# EXT_SEC.net
KiCad netlist of a schematic drawn in Altium Designer
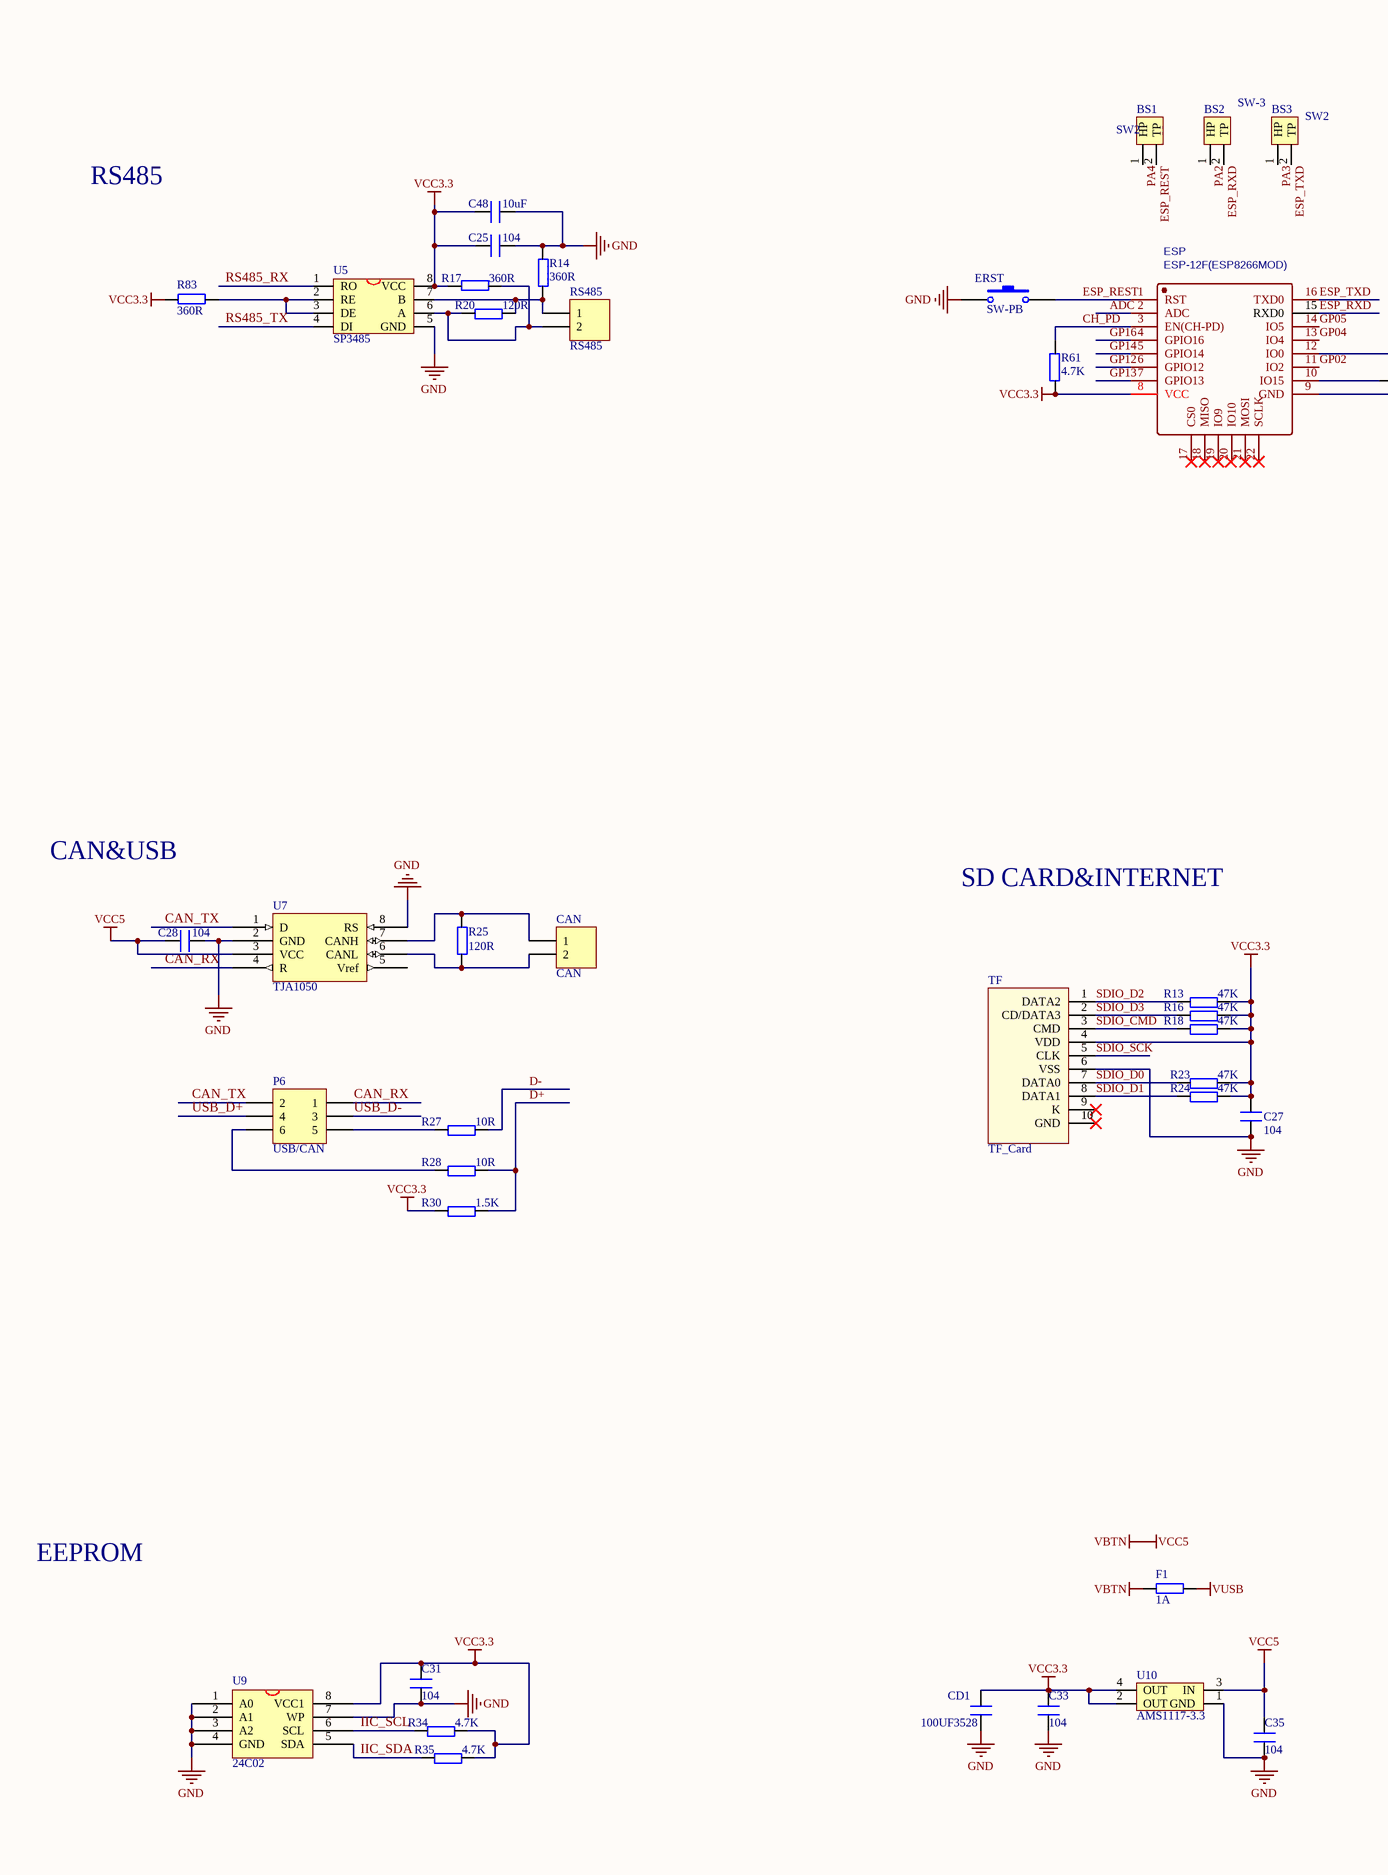
[diagram p0: EXT_SEC.SchDoc, left]
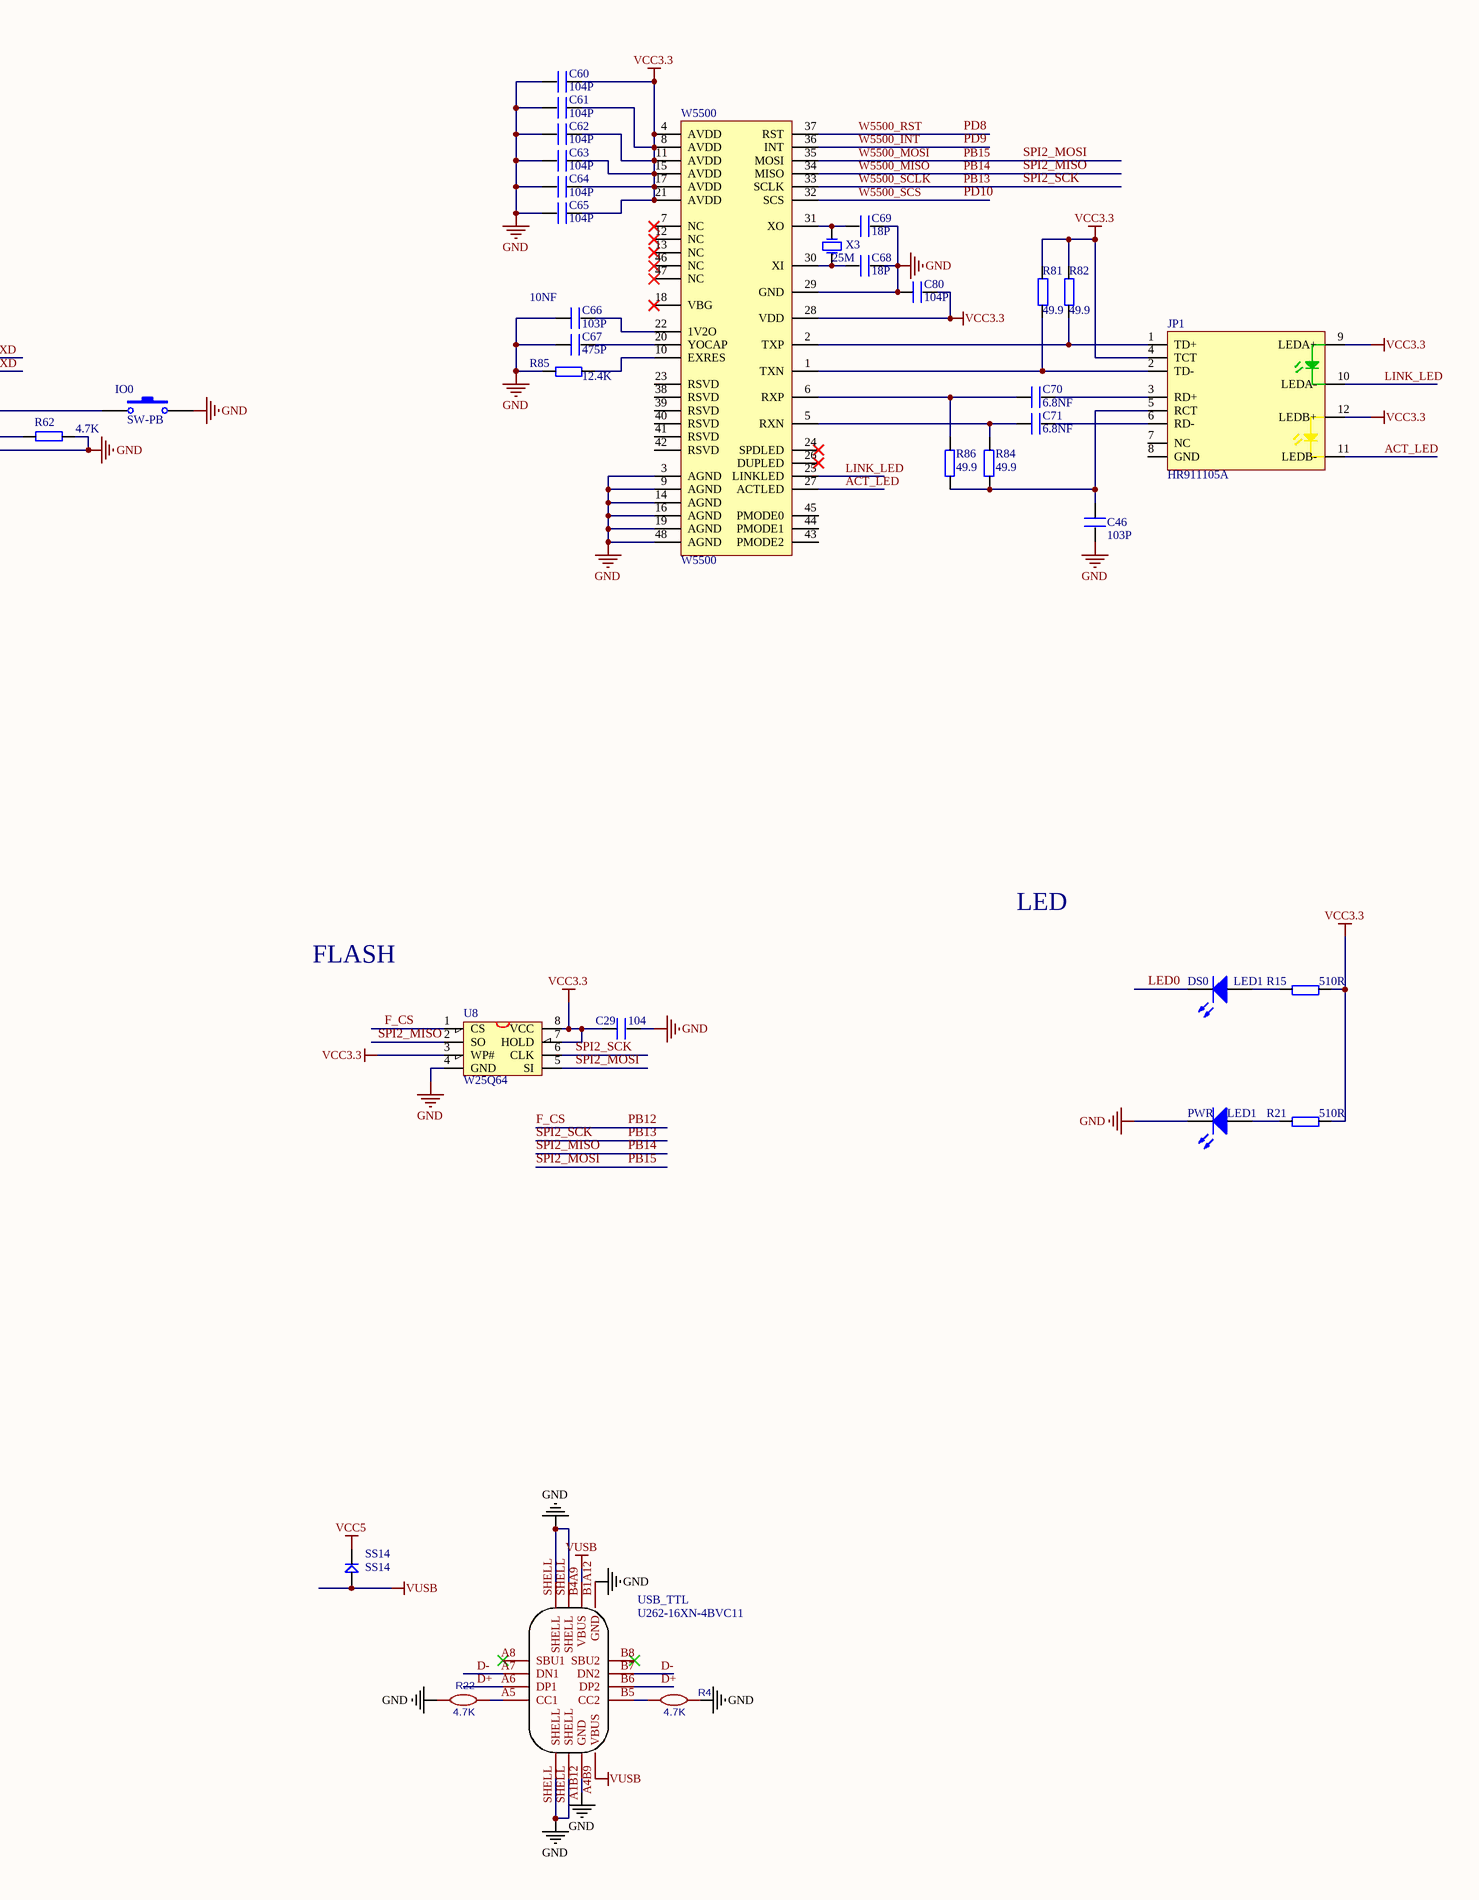
[diagram p1: EXT_SEC.SchDoc, right]

(export (version "E")
  (design (tool "Eeschema 10.0.6"))
  (components
    (comp (ref "BS1")
      (value "SW2")
      (footprint "SW-2")
      (description "SW-3")
      (libsource (lib "0.96OLED") (part "SW2"))
    )
    (comp (ref "BS2") (value "SW-3") (footprint "SW-2") (libsource (lib "0.96OLED") (part "SW2")))
    (comp (ref "BS3")
      (value "SW2")
      (footprint "SW-2")
      (description "SW-3")
      (libsource (lib "0.96OLED") (part "SW2"))
    )
    (comp (ref "C25") (value "104") (footprint "0603CL") (libsource (lib "战舰STM32开发板底板封装库") (part "C")))
    (comp (ref "C27") (value "104") (footprint "0603CL") (libsource (lib "CORE") (part "C")))
    (comp (ref "C28") (value "104") (footprint "0603CL") (libsource (lib "战舰STM32开发板底板封装库") (part "C")))
    (comp (ref "C29") (value "104") (footprint "0603CL") (libsource (lib "战舰STM32开发板底板封装库") (part "C")))
    (comp (ref "C31") (value "104") (footprint "0603CL") (libsource (lib "战舰STM32开发板底板封装库") (part "C")))
    (comp (ref "C33") (value "104") (footprint "0603CL") (libsource (lib "战舰STM32开发板底板封装库") (part "C")))
    (comp (ref "C35") (value "104") (footprint "0603CL") (libsource (lib "战舰STM32开发板底板封装库") (part "C")))
    (comp (ref "C46")
      (value "103P")
      (footprint "0603C")
      (description "风华 0603B103K500NT")
      (libsource (lib "ATK-SIM900A") (part "C"))
    )
    (comp (ref "C48") (value "10uF") (footprint "0603CL") (libsource (lib "战舰STM32开发板底板封装库") (part "C")))
    (comp (ref "C60")
      (value "104P")
      (footprint "0603C")
      (description "风华 0603B103K500NT")
      (libsource (lib "ATK-SIM900A") (part "C"))
    )
    (comp (ref "C61")
      (value "104P")
      (footprint "0603C")
      (description "风华 0603B103K500NT")
      (libsource (lib "ATK-SIM900A") (part "C"))
    )
    (comp (ref "C62")
      (value "104P")
      (footprint "0603C")
      (description "风华 0603B103K500NT")
      (libsource (lib "ATK-SIM900A") (part "C"))
    )
    (comp (ref "C63")
      (value "104P")
      (footprint "0603C")
      (description "风华 0603B103K500NT")
      (libsource (lib "ATK-SIM900A") (part "C"))
    )
    (comp (ref "C64")
      (value "104P")
      (footprint "0603C")
      (description "风华 0603B103K500NT")
      (libsource (lib "ATK-SIM900A") (part "C"))
    )
    (comp (ref "C65")
      (value "104P")
      (footprint "0603C")
      (description "风华 0603B103K500NT")
      (libsource (lib "ATK-SIM900A") (part "C"))
    )
    (comp (ref "C66")
      (value "103P")
      (footprint "0603C")
      (description "风华 0603B103K500NT")
      (libsource (lib "ATK-SIM900A") (part "C"))
    )
    (comp (ref "C67")
      (value "475P")
      (footprint "0603C")
      (description "风华 0603B103K500NT")
      (libsource (lib "ATK-SIM900A") (part "C"))
    )
    (comp (ref "C68")
      (value "18P")
      (footprint "0603C")
      (description "风华 0603B103K500NT")
      (libsource (lib "ATK-SIM900A") (part "C"))
    )
    (comp (ref "C69")
      (value "18P")
      (footprint "0603C")
      (description "风华 0603B103K500NT")
      (libsource (lib "ATK-SIM900A") (part "C"))
    )
    (comp (ref "C70")
      (value "6.8NF")
      (footprint "0603C")
      (description "风华 0603B103K500NT")
      (libsource (lib "ATK-SIM900A") (part "C"))
    )
    (comp (ref "C71")
      (value "6.8NF")
      (footprint "0603C")
      (description "风华 0603B103K500NT")
      (libsource (lib "ATK-SIM900A") (part "C"))
    )
    (comp (ref "C80")
      (value "104P")
      (footprint "0603C")
      (description "风华 0603B103K500NT")
      (libsource (lib "ATK-SIM900A") (part "C"))
    )
    (comp (ref "CAN")
      (value "CAN")
      (footprint "HEAD2L-0.8L")
      (description "Header, 2-Pin")
      (fields (field (name "PUBLISHER") "Altium Limited"))
      (libsource (lib "Miscellaneous Connectors") (part "Header 2"))
    )
    (comp (ref "CD1") (value "100UF3528") (footprint "3528") (libsource (lib "底板封装库") (part "C")))
    (comp (ref "DS0")
      (value "LED1")
      (footprint "0603d")
      (description "Typical RED, GREEN, YELLOW, AMBER GaAs LED")
      (fields (field (name "PUBLISHER") "Altium Limited"))
      (libsource (lib "战舰STM32开发板底板封装库") (part "LED2"))
    )
    (comp (ref "ERST")
      (value "SW-PB")
      (footprint "SW2 - MINI1")
      (description "Switch")
      (fields (field (name "PUBLISHER") "Altium Limited"))
      (libsource (lib "Miscellaneous Devices") (part "SW-PB"))
    )
    (comp (ref "ESP")
      (value "ESP-12F(ESP8266MOD)")
      (footprint "ESP12F")
      (fields (field (name "BOM_SUPPLIER PART") "C82891"))
      (libsource (lib "altium-import") (part "root_0_ESP-12F(ESP8266MOD)_"))
    )
    (comp (ref "F1") (value "1A") (footprint "0805") (libsource (lib "战舰STM32开发板底板封装库") (part "R")))
    (comp (ref "IO0")
      (value "SW-PB")
      (footprint "SW2 - MINI1")
      (description "Switch")
      (fields (field (name "PUBLISHER") "Altium Limited"))
      (libsource (lib "Miscellaneous Devices") (part "SW-PB"))
    )
    (comp (ref "JP1") (value "HR911105A") (footprint "HR911105A") (libsource (lib "原理图库") (part "HR911105A")))
    (comp (ref "P6")
      (value "USB/CAN")
      (footprint "HDR2X3L")
      (description "Header, 3-Pin, Dual row")
      (fields (field (name "PUBLISHER") "Altium Limited"))
      (libsource (lib "战舰STM32开发板底板封装库") (part "Header 3X2"))
    )
    (comp (ref "PWR")
      (value "LED1")
      (footprint "0603d")
      (description "Typical RED, GREEN, YELLOW, AMBER GaAs LED")
      (fields (field (name "PUBLISHER") "Altium Limited"))
      (libsource (lib "战舰STM32开发板底板封装库") (part "LED2"))
    )
    (comp (ref "R4")
      (value "4.7K")
      (footprint "R0603")
      (fields
        (field (name "BOM_SUPPLIER PART") "C269696")
        (field (name "BOM_MANUFACTURER PART") "RMC06035.1K5%N")
        (field (name "CONTRIBUTOR") "LCSC")
      )
      (libsource (lib "altium-import") (part "root_0_5.1K_"))
    )
    (comp (ref "R13") (value "47K") (footprint "0603L") (libsource (lib "CORE") (part "R")))
    (comp (ref "R14") (value "360R") (footprint "0603L") (libsource (lib "战舰STM32开发板底板封装库") (part "R")))
    (comp (ref "R15") (value "510R") (footprint "0603L") (libsource (lib "战舰STM32开发板底板封装库") (part "R")))
    (comp (ref "R16") (value "47K") (footprint "0603L") (libsource (lib "CORE") (part "R")))
    (comp (ref "R17") (value "360R") (footprint "0603L") (libsource (lib "战舰STM32开发板底板封装库") (part "R")))
    (comp (ref "R18") (value "47K") (footprint "0603L") (libsource (lib "CORE") (part "R")))
    (comp (ref "R20") (value "120R") (footprint "0603L") (libsource (lib "战舰STM32开发板底板封装库") (part "R")))
    (comp (ref "R21") (value "510R") (footprint "0603L") (libsource (lib "战舰STM32开发板底板封装库") (part "R")))
    (comp (ref "R22")
      (value "4.7K")
      (footprint "R0603")
      (fields
        (field (name "BOM_SUPPLIER PART") "C269696")
        (field (name "BOM_MANUFACTURER PART") "RMC06035.1K5%N")
        (field (name "CONTRIBUTOR") "LCSC")
      )
      (libsource (lib "altium-import") (part "root_0_5.1K_"))
    )
    (comp (ref "R23") (value "47K") (footprint "0603L") (libsource (lib "CORE") (part "R")))
    (comp (ref "R24") (value "47K") (footprint "0603L") (libsource (lib "CORE") (part "R")))
    (comp (ref "R25") (value "120R") (footprint "0603L") (libsource (lib "战舰STM32开发板底板封装库") (part "R")))
    (comp (ref "R27") (value "10R") (footprint "0603L") (libsource (lib "战舰STM32开发板底板封装库") (part "R")))
    (comp (ref "R28") (value "10R") (footprint "0603L") (libsource (lib "战舰STM32开发板底板封装库") (part "R")))
    (comp (ref "R30") (value "1.5K") (footprint "0603L") (libsource (lib "战舰STM32开发板底板封装库") (part "R")))
    (comp (ref "R34") (value "4.7K") (footprint "0603L") (libsource (lib "战舰STM32开发板底板封装库") (part "R")))
    (comp (ref "R35") (value "4.7K") (footprint "0603L") (libsource (lib "战舰STM32开发板底板封装库") (part "R")))
    (comp (ref "R61") (value "4.7K") (footprint "0603R") (libsource (lib "ENC28J60网络模块封装库") (part "R")))
    (comp (ref "R62") (value "4.7K") (footprint "0603R") (libsource (lib "ENC28J60网络模块封装库") (part "R")))
    (comp (ref "R81") (value "49.9") (footprint "0603R") (libsource (lib "ENC28J60网络模块封装库") (part "R")))
    (comp (ref "R82") (value "49.9") (footprint "0603R") (libsource (lib "ENC28J60网络模块封装库") (part "R")))
    (comp (ref "R83") (value "360R") (footprint "0603L") (libsource (lib "ENC28J60网络模块封装库") (part "R")))
    (comp (ref "R84") (value "49.9") (footprint "0603R") (libsource (lib "ENC28J60网络模块封装库") (part "R")))
    (comp (ref "R85") (value "12.4K") (footprint "0603R") (libsource (lib "ENC28J60网络模块封装库") (part "R")))
    (comp (ref "R86") (value "49.9") (footprint "0603R") (libsource (lib "ENC28J60网络模块封装库") (part "R")))
    (comp (ref "RS485")
      (value "RS485")
      (footprint "HEAD2L-0.8L")
      (description "Header, 2-Pin")
      (fields (field (name "PUBLISHER") "Altium Limited"))
      (libsource (lib "Miscellaneous Connectors") (part "Header 2"))
    )
    (comp (ref "SS14")
      (value "SS14")
      (footprint "SOD323D")
      (description "1N4148")
      (libsource (lib "ATK-SIM900A") (part "D"))
    )
    (comp (ref "TF")
      (value "TF_Card")
      (footprint "Micro SD")
      (description "TF卡座")
      (libsource (lib "STM32F103_CORE_BOARD_V1.6") (part "TF_Card"))
    )
    (comp (ref "U5")
      (value "SP3485")
      (footprint "SOP-8L")
      (libsource (lib "战舰STM32开发板底板封装库") (part "MAX3485"))
    )
    (comp (ref "U7")
      (value "TJA1050")
      (footprint "SOP-8L")
      (libsource (lib "战舰STM32开发板底板封装库") (part "SN65HVD230D"))
    )
    (comp (ref "U8")
      (value "W25Q64")
      (footprint "SOIC-8L")
      (description "W25X16;SST25VF016;MX25L1605")
      (libsource (lib "战舰STM32开发板底板封装库") (part "W25X16"))
    )
    (comp (ref "U9") (value "24C02") (footprint "SOP-8L") (libsource (lib "战舰STM32开发板底板封装库") (part "24C256")))
    (comp (ref "U10")
      (value "AMS1117-3.3")
      (footprint "SOT89")
      (libsource (lib "战舰STM32开发板底板封装库") (part "AMS1117"))
    )
    (comp (ref "USB_TTL")
      (value "U262-16XN-4BVC11")
      (footprint "USB-C-SMD_TYPE-C16PIN")
      (fields (field (name "BOM_SUPPLIER PART") "C319148") (field (name "CONTRIBUTOR") "LCSC"))
      (libsource (lib "wchlink") (part "U262-16XN-4BVC11"))
    )
    (comp (ref "W5500") (value "W5500") (footprint "QFP-48") (libsource (lib "原理图库") (part "W5500")))
    (comp (ref "X3")
      (value "25M")
      (footprint "OSC-5032-2P")
      (description "Crystal Oscillator")
      (fields (field (name "PUBLISHER") "Altium Limited"))
      (libsource (lib "常用元件库") (part "XTAL_1"))
    )
  )
  (nets
    (net (code "1") (name "/ACT_LED") (class "Default")
      (node (ref "JP1") (pin "11") (pinfunction "LEDB-_11") (pintype "passive"))
      (node (ref "W5500") (pin "27") (pinfunction "ACTLED_27") (pintype "passive"))
    )
    (net (code "2") (name "/ADC") (class "Default")
      (node (ref "ESP") (pin "2") (pinfunction "ADC_2") (pintype "passive"))
    )
    (net (code "3") (name "/CAN_RX") (class "Default")
      (node (ref "P6") (pin "1") (pinfunction "1_1") (pintype "passive"))
      (node (ref "U7") (pin "4") (pinfunction "R_4") (pintype "output"))
    )
    (net (code "4") (name "/CAN_TX") (class "Default")
      (node (ref "P6") (pin "2") (pinfunction "2_2") (pintype "passive"))
      (node (ref "U7") (pin "1") (pinfunction "D_1") (pintype "input"))
    )
    (net (code "5") (name "/CH_PD") (class "Default")
      (node (ref "ESP") (pin "3") (pinfunction "EN(CH-PD)_3") (pintype "passive"))
      (node (ref "R61") (pin "1") (pintype "passive"))
    )
    (net (code "6") (name "/D+") (class "Default")
      (node (ref "R28") (pin "2") (pintype "passive"))
      (node (ref "R30") (pin "2") (pintype "passive"))
      (node (ref "USB_TTL") (pin "A6") (pinfunction "DP1_A6") (pintype "passive"))
      (node (ref "USB_TTL") (pin "B6") (pinfunction "DP2_B6") (pintype "passive"))
    )
    (net (code "7") (name "/D-") (class "Default")
      (node (ref "R27") (pin "2") (pintype "passive"))
      (node (ref "USB_TTL") (pin "A7") (pinfunction "DN1_A7") (pintype "passive"))
      (node (ref "USB_TTL") (pin "B7") (pinfunction "DN2_B7") (pintype "passive"))
    )
    (net (code "8") (name "/ESP_REST") (class "Default")
      (node (ref "BS1") (pin "2") (pinfunction "TP_2") (pintype "passive"))
      (node (ref "ERST") (pin "1") (pinfunction "1_1") (pintype "passive"))
      (node (ref "ESP") (pin "1") (pinfunction "RST_1") (pintype "passive"))
    )
    (net (code "9") (name "/ESP_RXD") (class "Default")
      (node (ref "BS2") (pin "2") (pinfunction "TP_2") (pintype "passive"))
      (node (ref "ESP") (pin "15") (pinfunction "RXD0_15") (pintype "passive"))
    )
    (net (code "10") (name "/ESP_TXD") (class "Default")
      (node (ref "BS3") (pin "2") (pinfunction "TP_2") (pintype "passive"))
      (node (ref "ESP") (pin "16") (pinfunction "TXD0_16") (pintype "passive"))
    )
    (net (code "11") (name "/F_CS") (class "Default")
      (node (ref "U8") (pin "1") (pinfunction "CS_1") (pintype "passive"))
    )
    (net (code "12") (name "/GP02") (class "Default")
      (node (ref "ESP") (pin "11") (pinfunction "IO2_11") (pintype "passive"))
    )
    (net (code "13") (name "/GP04") (class "Default")
      (node (ref "ESP") (pin "13") (pinfunction "IO4_13") (pintype "passive"))
    )
    (net (code "14") (name "/GP05") (class "Default")
      (node (ref "ESP") (pin "14") (pinfunction "IO5_14") (pintype "passive"))
    )
    (net (code "15") (name "/GP12") (class "Default")
      (node (ref "ESP") (pin "6") (pinfunction "GPIO12_6") (pintype "passive"))
    )
    (net (code "16") (name "/GP13") (class "Default")
      (node (ref "ESP") (pin "7") (pinfunction "GPIO13_7") (pintype "passive"))
    )
    (net (code "17") (name "/GP14") (class "Default")
      (node (ref "ESP") (pin "5") (pinfunction "GPIO14_5") (pintype "passive"))
    )
    (net (code "18") (name "/GP16") (class "Default")
      (node (ref "ESP") (pin "4") (pinfunction "GPIO16_4") (pintype "passive"))
    )
    (net (code "19") (name "/IIC_SCL") (class "Default")
      (node (ref "R34") (pin "1") (pintype "passive"))
      (node (ref "U9") (pin "6") (pinfunction "SCL_6") (pintype "passive"))
    )
    (net (code "20") (name "/IIC_SDA") (class "Default")
      (node (ref "R35") (pin "1") (pintype "passive"))
      (node (ref "U9") (pin "5") (pinfunction "SDA_5") (pintype "passive"))
    )
    (net (code "21") (name "/LED0") (class "Default")
      (node (ref "DS0") (pin "2") (pinfunction "K_2") (pintype "passive"))
    )
    (net (code "22") (name "/LINK_LED") (class "Default")
      (node (ref "JP1") (pin "10") (pinfunction "LEDA-_10") (pintype "passive"))
      (node (ref "W5500") (pin "25") (pinfunction "LINKLED_25") (pintype "passive"))
    )
    (net (code "23") (name "/PA2") (class "Default")
      (node (ref "BS2") (pin "1") (pinfunction "HP_1") (pintype "passive"))
    )
    (net (code "24") (name "/PA3") (class "Default")
      (node (ref "BS3") (pin "1") (pinfunction "HP_1") (pintype "passive"))
    )
    (net (code "25") (name "/PA4") (class "Default")
      (node (ref "BS1") (pin "1") (pinfunction "HP_1") (pintype "passive"))
    )
    (net (code "26") (name "/PB13") (class "Default")
      (node (ref "U8") (pin "6") (pinfunction "CLK_6") (pintype "passive"))
      (node (ref "W5500") (pin "33") (pinfunction "SCLK_33") (pintype "passive"))
    )
    (net (code "27") (name "/PB14") (class "Default")
      (node (ref "U8") (pin "2") (pinfunction "SO_2") (pintype "passive"))
      (node (ref "W5500") (pin "34") (pinfunction "MISO_34") (pintype "passive"))
    )
    (net (code "28") (name "/PB15") (class "Default")
      (node (ref "U8") (pin "5") (pinfunction "SI_5") (pintype "passive"))
      (node (ref "W5500") (pin "35") (pinfunction "MOSI_35") (pintype "passive"))
    )
    (net (code "29") (name "/PD8") (class "Default")
      (node (ref "W5500") (pin "37") (pinfunction "RST_37") (pintype "passive"))
    )
    (net (code "30") (name "/PD9") (class "Default")
      (node (ref "W5500") (pin "36") (pinfunction "INT_36") (pintype "passive"))
    )
    (net (code "31") (name "/PD10") (class "Default")
      (node (ref "W5500") (pin "32") (pinfunction "SCS_32") (pintype "passive"))
    )
    (net (code "32") (name "/RS485_RX") (class "Default")
      (node (ref "U5") (pin "1") (pinfunction "RO_1") (pintype "passive"))
    )
    (net (code "33") (name "/RS485_TX") (class "Default")
      (node (ref "U5") (pin "4") (pinfunction "DI_4") (pintype "passive"))
    )
    (net (code "34") (name "/SDIO_CMD") (class "Default")
      (node (ref "R18") (pin "1") (pintype "passive"))
      (node (ref "TF") (pin "3") (pinfunction "CMD_3") (pintype "passive"))
    )
    (net (code "35") (name "/SDIO_D0") (class "Default")
      (node (ref "R23") (pin "1") (pintype "passive"))
      (node (ref "TF") (pin "7") (pinfunction "DATA0_7") (pintype "passive"))
    )
    (net (code "36") (name "/SDIO_D1") (class "Default")
      (node (ref "R24") (pin "1") (pintype "passive"))
      (node (ref "TF") (pin "8") (pinfunction "DATA1_8") (pintype "passive"))
    )
    (net (code "37") (name "/SDIO_D2") (class "Default")
      (node (ref "R13") (pin "1") (pintype "passive"))
      (node (ref "TF") (pin "1") (pinfunction "DATA2_1") (pintype "passive"))
    )
    (net (code "38") (name "/SDIO_D3") (class "Default")
      (node (ref "R16") (pin "1") (pintype "passive"))
      (node (ref "TF") (pin "2") (pinfunction "CD/DATA3_2") (pintype "passive"))
    )
    (net (code "39") (name "/SDIO_SCK") (class "Default")
      (node (ref "TF") (pin "5") (pinfunction "CLK_5") (pintype "passive"))
    )
    (net (code "40") (name "/USB_D+") (class "Default")
      (node (ref "P6") (pin "4") (pinfunction "4_4") (pintype "passive"))
    )
    (net (code "41") (name "/USB_D-") (class "Default")
      (node (ref "P6") (pin "3") (pinfunction "3_3") (pintype "passive"))
    )
    (net (code "42") (name "GND") (class "Default")
      (node (ref "C25") (pin "2") (pintype "passive"))
      (node (ref "C27") (pin "1") (pintype "passive"))
      (node (ref "C28") (pin "2") (pintype "passive"))
      (node (ref "C29") (pin "2") (pintype "passive"))
      (node (ref "C31") (pin "1") (pintype "passive"))
      (node (ref "C33") (pin "1") (pintype "passive"))
      (node (ref "C35") (pin "1") (pintype "passive"))
      (node (ref "C46") (pin "2") (pintype "passive"))
      (node (ref "C48") (pin "2") (pintype "passive"))
      (node (ref "C60") (pin "2") (pintype "passive"))
      (node (ref "C61") (pin "2") (pintype "passive"))
      (node (ref "C62") (pin "2") (pintype "passive"))
      (node (ref "C63") (pin "2") (pintype "passive"))
      (node (ref "C64") (pin "2") (pintype "passive"))
      (node (ref "C65") (pin "2") (pintype "passive"))
      (node (ref "C66") (pin "2") (pintype "passive"))
      (node (ref "C67") (pin "2") (pintype "passive"))
      (node (ref "C68") (pin "1") (pintype "passive"))
      (node (ref "C69") (pin "1") (pintype "passive"))
      (node (ref "C80") (pin "2") (pintype "passive"))
      (node (ref "CD1") (pin "A") (pintype "passive"))
      (node (ref "ERST") (pin "2") (pinfunction "2_2") (pintype "passive"))
      (node (ref "ESP") (pin "9") (pinfunction "GND_9") (pintype "passive"))
      (node (ref "IO0") (pin "1") (pinfunction "1_1") (pintype "passive"))
      (node (ref "PWR") (pin "2") (pinfunction "K_2") (pintype "passive"))
      (node (ref "R14") (pin "2") (pintype "passive"))
      (node (ref "R22") (pin "1") (pinfunction "1_1") (pintype "passive"))
      (node (ref "R4") (pin "2") (pinfunction "2_2") (pintype "passive"))
      (node (ref "R62") (pin "1") (pintype "passive"))
      (node (ref "R85") (pin "1") (pintype "passive"))
      (node (ref "TF") (pin "6") (pinfunction "VSS_6") (pintype "passive"))
      (node (ref "U10") (pin "1") (pinfunction "GND_1") (pintype "passive"))
      (node (ref "U5") (pin "5") (pinfunction "GND_5") (pintype "passive"))
      (node (ref "U7") (pin "2") (pinfunction "GND_2") (pintype "power_in"))
      (node (ref "U7") (pin "8") (pinfunction "RS_8") (pintype "input"))
      (node (ref "U8") (pin "4") (pinfunction "GND_4") (pintype "passive"))
      (node (ref "U9") (pin "1") (pinfunction "A0_1") (pintype "passive"))
      (node (ref "U9") (pin "2") (pinfunction "A1_2") (pintype "passive"))
      (node (ref "U9") (pin "3") (pinfunction "A2_3") (pintype "passive"))
      (node (ref "U9") (pin "4") (pinfunction "GND_4") (pintype "passive"))
      (node (ref "U9") (pin "7") (pinfunction "WP_7") (pintype "passive"))
      (node (ref "USB_TTL") (pin "A1B12") (pinfunction "GND_A1B12") (pintype "passive"))
      (node (ref "USB_TTL") (pin "B1A12") (pinfunction "GND_B1A12") (pintype "passive"))
      (node (ref "USB_TTL") (pin "SHELL") (pinfunction "SHELL_SHELL") (pintype "passive"))
      (node (ref "W5500") (pin "14") (pinfunction "AGND_14") (pintype "passive"))
      (node (ref "W5500") (pin "16") (pinfunction "AGND_16") (pintype "passive"))
      (node (ref "W5500") (pin "19") (pinfunction "AGND_19") (pintype "passive"))
      (node (ref "W5500") (pin "29") (pinfunction "GND_29") (pintype "passive"))
      (node (ref "W5500") (pin "3") (pinfunction "AGND_3") (pintype "passive"))
      (node (ref "W5500") (pin "48") (pinfunction "AGND_48") (pintype "passive"))
      (node (ref "W5500") (pin "9") (pinfunction "AGND_9") (pintype "passive"))
    )
    (net (code "43") (name "Net-(DS0-A)") (class "Default")
      (node (ref "DS0") (pin "1") (pinfunction "A_1") (pintype "passive"))
      (node (ref "R15") (pin "1") (pintype "passive"))
    )
    (net (code "44") (name "Net-(ESP-IO0)") (class "Default")
      (node (ref "ESP") (pin "12") (pinfunction "IO0_12") (pintype "passive"))
      (node (ref "IO0") (pin "2") (pinfunction "2_2") (pintype "passive"))
    )
    (net (code "45") (name "Net-(ESP-IO15)") (class "Default")
      (node (ref "ESP") (pin "10") (pinfunction "IO15_10") (pintype "passive"))
      (node (ref "R62") (pin "2") (pintype "passive"))
    )
    (net (code "46") (name "Net-(JP1-RCT)") (class "Default")
      (node (ref "C46") (pin "1") (pintype "passive"))
      (node (ref "JP1") (pin "5") (pinfunction "RCT_5") (pintype "passive"))
      (node (ref "R84") (pin "2") (pintype "passive"))
      (node (ref "R86") (pin "2") (pintype "passive"))
    )
    (net (code "47") (name "Net-(JP1-RD+)") (class "Default")
      (node (ref "C70") (pin "1") (pintype "passive"))
      (node (ref "JP1") (pin "3") (pinfunction "RD+_3") (pintype "passive"))
    )
    (net (code "48") (name "Net-(JP1-RD-)") (class "Default")
      (node (ref "C71") (pin "1") (pintype "passive"))
      (node (ref "JP1") (pin "6") (pinfunction "RD-_6") (pintype "passive"))
    )
    (net (code "49") (name "Net-(JP1-TD+)") (class "Default")
      (node (ref "JP1") (pin "1") (pinfunction "TD+_1") (pintype "passive"))
      (node (ref "R82") (pin "1") (pintype "passive"))
      (node (ref "W5500") (pin "2") (pinfunction "TXP_2") (pintype "passive"))
    )
    (net (code "50") (name "Net-(JP1-TD-)") (class "Default")
      (node (ref "JP1") (pin "2") (pinfunction "TD-_2") (pintype "passive"))
      (node (ref "R81") (pin "1") (pintype "passive"))
      (node (ref "W5500") (pin "1") (pinfunction "TXN_1") (pintype "passive"))
    )
    (net (code "51") (name "Net-(P6-Pad5)") (class "Default")
      (node (ref "P6") (pin "5") (pinfunction "5_5") (pintype "passive"))
      (node (ref "R27") (pin "1") (pintype "passive"))
    )
    (net (code "52") (name "Net-(P6-Pad6)") (class "Default")
      (node (ref "P6") (pin "6") (pinfunction "6_6") (pintype "passive"))
      (node (ref "R28") (pin "1") (pintype "passive"))
    )
    (net (code "53") (name "Net-(PWR-A)") (class "Default")
      (node (ref "PWR") (pin "1") (pinfunction "A_1") (pintype "passive"))
      (node (ref "R21") (pin "1") (pintype "passive"))
    )
    (net (code "54") (name "Net-(U5-A)") (class "Default")
      (node (ref "R17") (pin "1") (pintype "passive"))
      (node (ref "R20") (pin "1") (pintype "passive"))
      (node (ref "RS485") (pin "2") (pinfunction "2_2") (pintype "passive"))
      (node (ref "U5") (pin "6") (pinfunction "A_6") (pintype "passive"))
    )
    (net (code "55") (name "Net-(U5-B)") (class "Default")
      (node (ref "R14") (pin "1") (pintype "passive"))
      (node (ref "R20") (pin "2") (pintype "passive"))
      (node (ref "RS485") (pin "1") (pinfunction "1_1") (pintype "passive"))
      (node (ref "U5") (pin "7") (pinfunction "B_7") (pintype "passive"))
    )
    (net (code "56") (name "Net-(U5-DE)") (class "Default")
      (node (ref "R83") (pin "1") (pintype "passive"))
      (node (ref "U5") (pin "2") (pinfunction "RE_2") (pintype "passive"))
      (node (ref "U5") (pin "3") (pinfunction "DE_3") (pintype "passive"))
    )
    (net (code "57") (name "Net-(U7-CANH)") (class "Default")
      (node (ref "CAN") (pin "1") (pinfunction "1_1") (pintype "passive"))
      (node (ref "R25") (pin "2") (pintype "passive"))
      (node (ref "U7") (pin "7") (pinfunction "CANH_7") (pintype "bidirectional"))
    )
    (net (code "58") (name "Net-(U7-CANL)") (class "Default")
      (node (ref "CAN") (pin "2") (pinfunction "2_2") (pintype "passive"))
      (node (ref "R25") (pin "1") (pintype "passive"))
      (node (ref "U7") (pin "6") (pinfunction "CANL_6") (pintype "bidirectional"))
    )
    (net (code "59") (name "Net-(USB_TTL-CC1)") (class "Default")
      (node (ref "R22") (pin "2") (pinfunction "2_2") (pintype "passive"))
      (node (ref "USB_TTL") (pin "A5") (pinfunction "CC1_A5") (pintype "passive"))
    )
    (net (code "60") (name "Net-(USB_TTL-CC2)") (class "Default")
      (node (ref "R4") (pin "1") (pinfunction "1_1") (pintype "passive"))
      (node (ref "USB_TTL") (pin "B5") (pinfunction "CC2_B5") (pintype "passive"))
    )
    (net (code "61") (name "Net-(W5500-1V2O)") (class "Default")
      (node (ref "C66") (pin "1") (pintype "passive"))
      (node (ref "W5500") (pin "22") (pinfunction "1V2O_22") (pintype "passive"))
    )
    (net (code "62") (name "Net-(W5500-EXRES)") (class "Default")
      (node (ref "R85") (pin "2") (pintype "passive"))
      (node (ref "W5500") (pin "10") (pinfunction "EXRES_10") (pintype "passive"))
    )
    (net (code "63") (name "Net-(W5500-RXN)") (class "Default")
      (node (ref "C71") (pin "2") (pintype "passive"))
      (node (ref "R84") (pin "1") (pintype "passive"))
      (node (ref "W5500") (pin "5") (pinfunction "RXN_5") (pintype "passive"))
    )
    (net (code "64") (name "Net-(W5500-RXP)") (class "Default")
      (node (ref "C70") (pin "2") (pintype "passive"))
      (node (ref "R86") (pin "1") (pintype "passive"))
      (node (ref "W5500") (pin "6") (pinfunction "RXP_6") (pintype "passive"))
    )
    (net (code "65") (name "Net-(W5500-XI)") (class "Default")
      (node (ref "C68") (pin "2") (pintype "passive"))
      (node (ref "W5500") (pin "30") (pinfunction "XI_30") (pintype "passive"))
      (node (ref "X3") (pin "1") (pinfunction "OSC1_1") (pintype "passive"))
    )
    (net (code "66") (name "Net-(W5500-XO)") (class "Default")
      (node (ref "C69") (pin "2") (pintype "passive"))
      (node (ref "W5500") (pin "31") (pinfunction "XO_31") (pintype "passive"))
      (node (ref "X3") (pin "2") (pinfunction "OSC2_2") (pintype "passive"))
    )
    (net (code "67") (name "Net-(W5500-YOCAP)") (class "Default")
      (node (ref "C67") (pin "1") (pintype "passive"))
      (node (ref "W5500") (pin "20") (pinfunction "YOCAP_20") (pintype "passive"))
    )
    (net (code "68") (name "VBTN") (class "Default")
      (node (ref "C28") (pin "1") (pintype "passive"))
      (node (ref "C35") (pin "2") (pintype "passive"))
      (node (ref "F1") (pin "2") (pintype "passive"))
      (node (ref "SS14") (pin "2") (pintype "passive"))
      (node (ref "U10") (pin "3") (pinfunction "IN_3") (pintype "passive"))
      (node (ref "U7") (pin "3") (pinfunction "VCC_3") (pintype "power_in"))
    )
    (net (code "69") (name "VCC3.3") (class "Default")
      (node (ref "C25") (pin "1") (pintype "passive"))
      (node (ref "C27") (pin "2") (pintype "passive"))
      (node (ref "C29") (pin "1") (pintype "passive"))
      (node (ref "C31") (pin "2") (pintype "passive"))
      (node (ref "C33") (pin "2") (pintype "passive"))
      (node (ref "C48") (pin "1") (pintype "passive"))
      (node (ref "C60") (pin "1") (pintype "passive"))
      (node (ref "C61") (pin "1") (pintype "passive"))
      (node (ref "C62") (pin "1") (pintype "passive"))
      (node (ref "C63") (pin "1") (pintype "passive"))
      (node (ref "C64") (pin "1") (pintype "passive"))
      (node (ref "C65") (pin "1") (pintype "passive"))
      (node (ref "C80") (pin "1") (pintype "passive"))
      (node (ref "CD1") (pin "K") (pintype "passive"))
      (node (ref "ESP") (pin "8") (pinfunction "VCC_8") (pintype "passive"))
      (node (ref "JP1") (pin "12") (pinfunction "LEDB+_12") (pintype "passive"))
      (node (ref "JP1") (pin "4") (pinfunction "TCT_4") (pintype "passive"))
      (node (ref "JP1") (pin "9") (pinfunction "LEDA+_9") (pintype "passive"))
      (node (ref "R13") (pin "2") (pintype "passive"))
      (node (ref "R15") (pin "2") (pintype "passive"))
      (node (ref "R16") (pin "2") (pintype "passive"))
      (node (ref "R17") (pin "2") (pintype "passive"))
      (node (ref "R18") (pin "2") (pintype "passive"))
      (node (ref "R21") (pin "2") (pintype "passive"))
      (node (ref "R23") (pin "2") (pintype "passive"))
      (node (ref "R24") (pin "2") (pintype "passive"))
      (node (ref "R30") (pin "1") (pintype "passive"))
      (node (ref "R34") (pin "2") (pintype "passive"))
      (node (ref "R35") (pin "2") (pintype "passive"))
      (node (ref "R61") (pin "2") (pintype "passive"))
      (node (ref "R81") (pin "2") (pintype "passive"))
      (node (ref "R82") (pin "2") (pintype "passive"))
      (node (ref "R83") (pin "2") (pintype "passive"))
      (node (ref "TF") (pin "4") (pinfunction "VDD_4") (pintype "passive"))
      (node (ref "U10") (pin "2") (pinfunction "OUT_2") (pintype "passive"))
      (node (ref "U10") (pin "4") (pinfunction "OUT_4") (pintype "passive"))
      (node (ref "U5") (pin "8") (pinfunction "VCC_8") (pintype "passive"))
      (node (ref "U8") (pin "3") (pinfunction "WP#_3") (pintype "passive"))
      (node (ref "U8") (pin "7") (pinfunction "HOLD_7") (pintype "passive"))
      (node (ref "U8") (pin "8") (pinfunction "VCC_8") (pintype "passive"))
      (node (ref "U9") (pin "8") (pinfunction "VCC1_8") (pintype "passive"))
      (node (ref "W5500") (pin "11") (pinfunction "AVDD_11") (pintype "passive"))
      (node (ref "W5500") (pin "15") (pinfunction "AVDD_15") (pintype "passive"))
      (node (ref "W5500") (pin "17") (pinfunction "AVDD_17") (pintype "passive"))
      (node (ref "W5500") (pin "21") (pinfunction "AVDD_21") (pintype "passive"))
      (node (ref "W5500") (pin "28") (pinfunction "VDD_28") (pintype "passive"))
      (node (ref "W5500") (pin "4") (pinfunction "AVDD_4") (pintype "passive"))
      (node (ref "W5500") (pin "8") (pinfunction "AVDD_8") (pintype "passive"))
    )
    (net (code "70") (name "VUSB") (class "Default")
      (node (ref "F1") (pin "1") (pintype "passive"))
      (node (ref "SS14") (pin "1") (pintype "passive"))
      (node (ref "USB_TTL") (pin "A4B9") (pinfunction "VBUS_A4B9") (pintype "passive"))
      (node (ref "USB_TTL") (pin "B4A9") (pinfunction "VBUS_B4A9") (pintype "passive"))
    )
    (net (code "71") (name "unconnected-(ESP-CS0-Pad17)") (class "Default")
      (node (ref "ESP") (pin "17") (pinfunction "CS0_17") (pintype "passive+no_connect"))
    )
    (net (code "72") (name "unconnected-(ESP-IO9-Pad19)") (class "Default")
      (node (ref "ESP") (pin "19") (pinfunction "IO9_19") (pintype "passive+no_connect"))
    )
    (net (code "73") (name "unconnected-(ESP-IO10-Pad20)") (class "Default")
      (node (ref "ESP") (pin "20") (pinfunction "IO10_20") (pintype "passive"))
    )
    (net (code "74") (name "unconnected-(ESP-MISO-Pad18)") (class "Default")
      (node (ref "ESP") (pin "18") (pinfunction "MISO_18") (pintype "passive+no_connect"))
    )
    (net (code "75") (name "unconnected-(ESP-MOSI-Pad21)") (class "Default")
      (node (ref "ESP") (pin "21") (pinfunction "MOSI_21") (pintype "passive+no_connect"))
    )
    (net (code "76") (name "unconnected-(ESP-SCLK-Pad22)") (class "Default")
      (node (ref "ESP") (pin "22") (pinfunction "SCLK_22") (pintype "passive+no_connect"))
    )
    (net (code "77") (name "unconnected-(JP1-GND-Pad8)") (class "Default")
      (node (ref "JP1") (pin "8") (pinfunction "GND_8") (pintype "passive"))
    )
    (net (code "78") (name "unconnected-(JP1-NC-Pad7)") (class "Default")
      (node (ref "JP1") (pin "7") (pinfunction "NC_7") (pintype "passive"))
    )
    (net (code "79") (name "unconnected-(TF-GND-Pad10)") (class "Default")
      (node (ref "TF") (pin "10") (pinfunction "GND_10") (pintype "passive+no_connect"))
    )
    (net (code "80") (name "unconnected-(TF-K-Pad9)") (class "Default")
      (node (ref "TF") (pin "9") (pinfunction "K_9") (pintype "passive+no_connect"))
    )
    (net (code "81") (name "unconnected-(U7-Vref-Pad5)") (class "Default")
      (node (ref "U7") (pin "5") (pinfunction "Vref_5") (pintype "output"))
    )
    (net (code "82") (name "unconnected-(USB_TTL-SBU1-PadA8)") (class "Default")
      (node (ref "USB_TTL") (pin "A8") (pinfunction "SBU1_A8") (pintype "passive+no_connect"))
    )
    (net (code "83") (name "unconnected-(USB_TTL-SBU2-PadB8)") (class "Default")
      (node (ref "USB_TTL") (pin "B8") (pinfunction "SBU2_B8") (pintype "passive+no_connect"))
    )
    (net (code "84") (name "unconnected-(W5500-DUPLED-Pad26)") (class "Default")
      (node (ref "W5500") (pin "26") (pinfunction "DUPLED_26") (pintype "passive+no_connect"))
    )
    (net (code "85") (name "unconnected-(W5500-NC-Pad7)") (class "Default")
      (node (ref "W5500") (pin "7") (pinfunction "NC_7") (pintype "passive+no_connect"))
    )
    (net (code "86") (name "unconnected-(W5500-NC-Pad12)") (class "Default")
      (node (ref "W5500") (pin "12") (pinfunction "NC_12") (pintype "passive+no_connect"))
    )
    (net (code "87") (name "unconnected-(W5500-NC-Pad13)") (class "Default")
      (node (ref "W5500") (pin "13") (pinfunction "NC_13") (pintype "passive+no_connect"))
    )
    (net (code "88") (name "unconnected-(W5500-NC-Pad46)") (class "Default")
      (node (ref "W5500") (pin "46") (pinfunction "NC_46") (pintype "passive+no_connect"))
    )
    (net (code "89") (name "unconnected-(W5500-NC-Pad47)") (class "Default")
      (node (ref "W5500") (pin "47") (pinfunction "NC_47") (pintype "passive+no_connect"))
    )
    (net (code "90") (name "unconnected-(W5500-PMODE0-Pad45)") (class "Default")
      (node (ref "W5500") (pin "45") (pinfunction "PMODE0_45") (pintype "passive"))
    )
    (net (code "91") (name "unconnected-(W5500-PMODE1-Pad44)") (class "Default")
      (node (ref "W5500") (pin "44") (pinfunction "PMODE1_44") (pintype "passive"))
    )
    (net (code "92") (name "unconnected-(W5500-PMODE2-Pad43)") (class "Default")
      (node (ref "W5500") (pin "43") (pinfunction "PMODE2_43") (pintype "passive"))
    )
    (net (code "93") (name "unconnected-(W5500-RSVD-Pad23)") (class "Default")
      (node (ref "W5500") (pin "23") (pinfunction "RSVD_23") (pintype "passive"))
    )
    (net (code "94") (name "unconnected-(W5500-RSVD-Pad38)") (class "Default")
      (node (ref "W5500") (pin "38") (pinfunction "RSVD_38") (pintype "passive"))
    )
    (net (code "95") (name "unconnected-(W5500-RSVD-Pad39)") (class "Default")
      (node (ref "W5500") (pin "39") (pinfunction "RSVD_39") (pintype "passive"))
    )
    (net (code "96") (name "unconnected-(W5500-RSVD-Pad40)") (class "Default")
      (node (ref "W5500") (pin "40") (pinfunction "RSVD_40") (pintype "passive"))
    )
    (net (code "97") (name "unconnected-(W5500-RSVD-Pad41)") (class "Default")
      (node (ref "W5500") (pin "41") (pinfunction "RSVD_41") (pintype "passive"))
    )
    (net (code "98") (name "unconnected-(W5500-RSVD-Pad42)") (class "Default")
      (node (ref "W5500") (pin "42") (pinfunction "RSVD_42") (pintype "passive"))
    )
    (net (code "99") (name "unconnected-(W5500-SPDLED-Pad24)") (class "Default")
      (node (ref "W5500") (pin "24") (pinfunction "SPDLED_24") (pintype "passive+no_connect"))
    )
    (net (code "100") (name "unconnected-(W5500-VBG-Pad18)") (class "Default")
      (node (ref "W5500") (pin "18") (pinfunction "VBG_18") (pintype "passive+no_connect"))
    )
  )
)
